# biggity.net
KiCad netlist of a schematic drawn in EAGLE
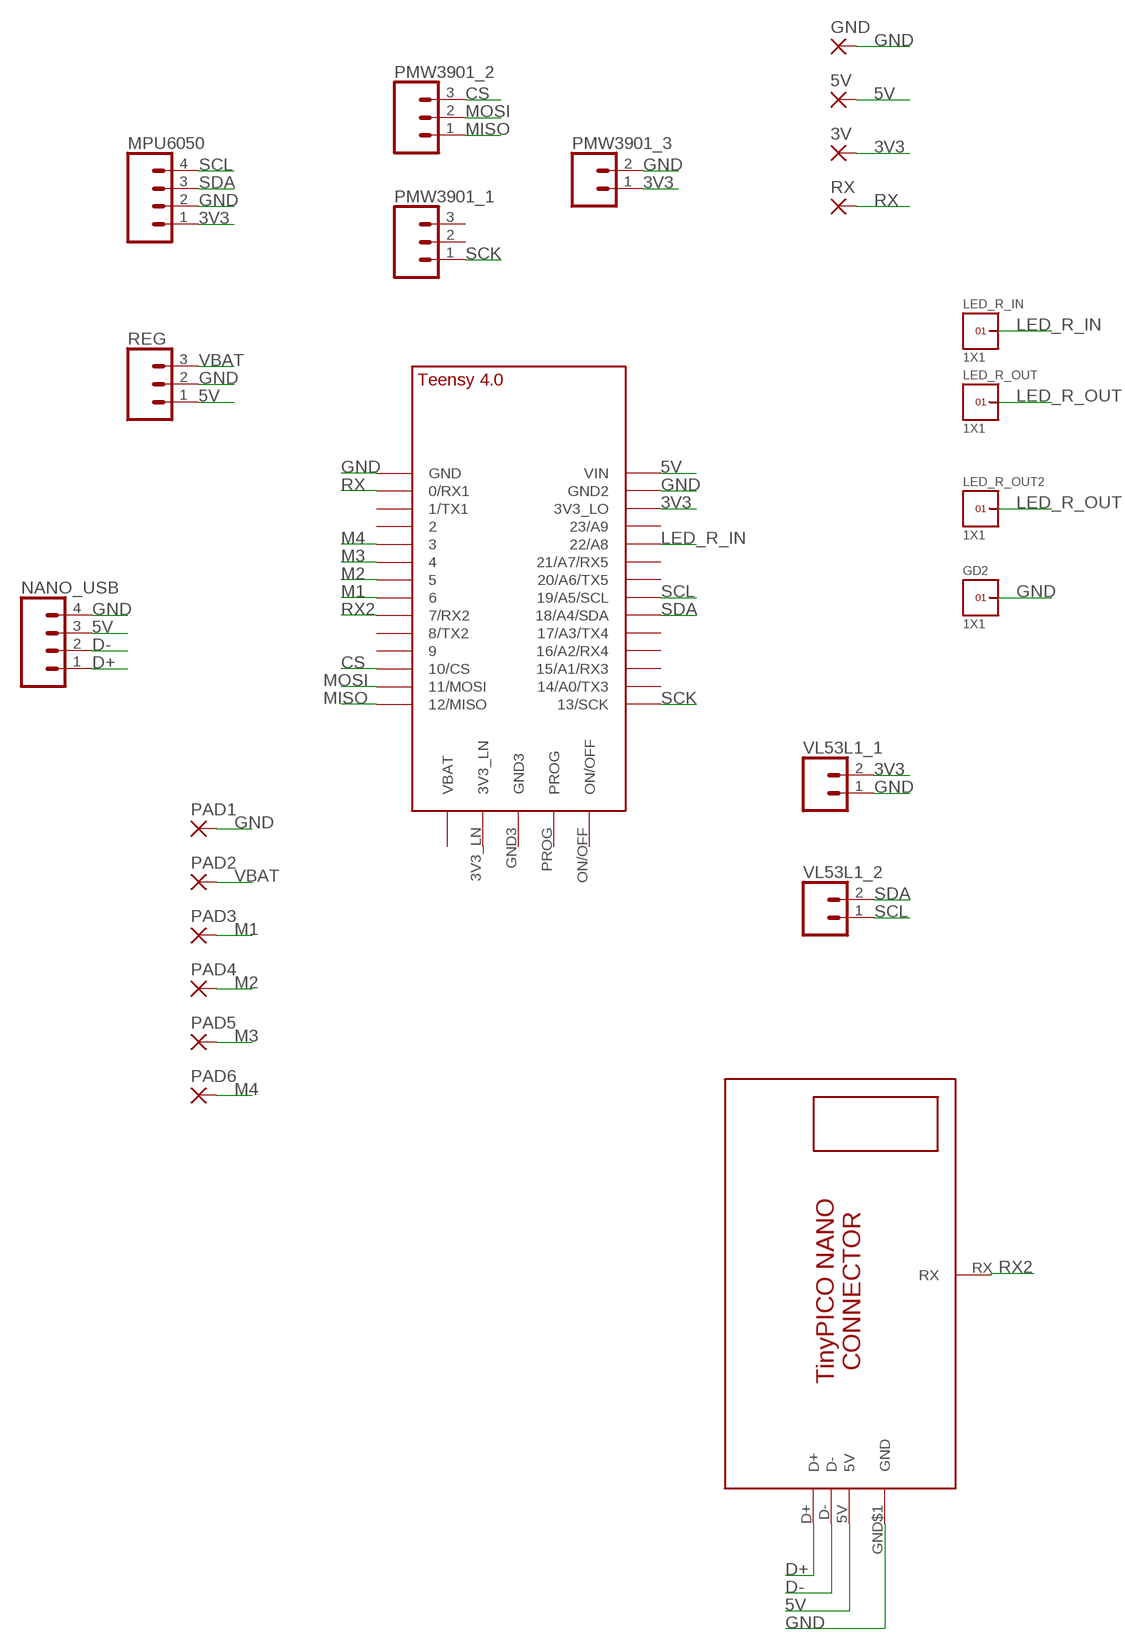
[diagram p0: schematic, sheet 1]

(export (version "E")
  (design (tool "Eeschema 10.0.6"))
  (components
    (comp (ref "3V")
      (value "SMD2")
      (footprint "eagle-import:SMD1,27-2,54")
      (libsource (lib "eagle-import") (part "SMD2"))
    )
    (comp (ref "5V")
      (value "SMD2")
      (footprint "eagle-import:SMD1,27-2,54")
      (libsource (lib "eagle-import") (part "SMD2"))
    )
    (comp (ref "GD2")
      (value "1X1")
      (footprint "eagle-import:1X1")
      (libsource (lib "eagle-import") (part "1X1"))
    )
    (comp (ref "GND")
      (value "SMD2")
      (footprint "eagle-import:SMD1,27-2,54")
      (libsource (lib "eagle-import") (part "SMD2"))
    )
    (comp (ref "LED_R_IN")
      (value "1X1")
      (footprint "eagle-import:1X1")
      (libsource (lib "eagle-import") (part "1X1"))
    )
    (comp (ref "LED_R_OUT")
      (value "1X1")
      (footprint "eagle-import:1X1")
      (libsource (lib "eagle-import") (part "1X1"))
    )
    (comp (ref "LED_R_OUT2")
      (value "1X1")
      (footprint "eagle-import:1X1")
      (libsource (lib "eagle-import") (part "1X1"))
    )
    (comp (ref "MPU6050")
      (value "CONN_041X04_NO_SILK")
      (footprint "eagle-import:1X04_NO_SILK")
      (libsource (lib "eagle-import") (part "CONN_041X04_NO_SILK"))
    )
    (comp (ref "NANO_USB")
      (value "CONN_041X04_NO_SILK")
      (footprint "eagle-import:1X04_NO_SILK")
      (libsource (lib "eagle-import") (part "CONN_041X04_NO_SILK"))
    )
    (comp (ref "PAD1")
      (value "SMD2")
      (footprint "eagle-import:SMD1,27-2,54")
      (libsource (lib "eagle-import") (part "SMD2"))
    )
    (comp (ref "PAD2")
      (value "SMD2")
      (footprint "eagle-import:SMD1,27-2,54")
      (libsource (lib "eagle-import") (part "SMD2"))
    )
    (comp (ref "PAD3")
      (value "SMD2")
      (footprint "eagle-import:SMD1,27-2,54")
      (libsource (lib "eagle-import") (part "SMD2"))
    )
    (comp (ref "PAD4")
      (value "SMD2")
      (footprint "eagle-import:SMD1,27-2,54")
      (libsource (lib "eagle-import") (part "SMD2"))
    )
    (comp (ref "PAD5")
      (value "SMD2")
      (footprint "eagle-import:SMD1,27-2,54")
      (libsource (lib "eagle-import") (part "SMD2"))
    )
    (comp (ref "PAD6")
      (value "SMD2")
      (footprint "eagle-import:SMD1,27-2,54")
      (libsource (lib "eagle-import") (part "SMD2"))
    )
    (comp (ref "PMW3901_1")
      (value "CONN_031X03_NO_SILK")
      (footprint "eagle-import:1X03_NO_SILK")
      (libsource (lib "eagle-import") (part "CONN_031X03_NO_SILK"))
    )
    (comp (ref "PMW3901_2")
      (value "CONN_031X03_NO_SILK")
      (footprint "eagle-import:1X03_NO_SILK")
      (libsource (lib "eagle-import") (part "CONN_031X03_NO_SILK"))
    )
    (comp (ref "PMW3901_3")
      (value "CONN_021X02_NO_SILK")
      (footprint "eagle-import:1X02_NO_SILK")
      (libsource (lib "eagle-import") (part "CONN_021X02_NO_SILK"))
    )
    (comp (ref "REG")
      (value "CONN_031X03_NO_SILK")
      (footprint "eagle-import:1X03_NO_SILK")
      (libsource (lib "eagle-import") (part "CONN_031X03_NO_SILK"))
    )
    (comp (ref "RX")
      (value "SMD2")
      (footprint "eagle-import:SMD1,27-2,54")
      (libsource (lib "eagle-import") (part "SMD2"))
    )
    (comp (ref "U$1")
      (value "TEENSY_4.0")
      (footprint "eagle-import:TEENSY_4.0")
      (libsource (lib "eagle-import") (part "TEENSY_4.0"))
    )
    (comp (ref "U$2")
      (value "TINYPICO-NANO-CONNECTOR")
      (footprint "eagle-import:TINYPICO-NANO-CONNECTOR")
      (libsource (lib "eagle-import") (part "TINYPICO-NANO-CONNECTOR"))
    )
    (comp (ref "VL53L1_1")
      (value "CONN_021X02_NO_SILK")
      (footprint "eagle-import:1X02_NO_SILK")
      (libsource (lib "eagle-import") (part "CONN_021X02_NO_SILK"))
    )
    (comp (ref "VL53L1_2")
      (value "CONN_021X02_NO_SILK")
      (footprint "eagle-import:1X02_NO_SILK")
      (libsource (lib "eagle-import") (part "CONN_021X02_NO_SILK"))
    )
  )
  (nets
    (net (code "1") (name "/3V3") (class "Default")
      (node (ref "3V") (pin "1") (pinfunction "P_1") (pintype "passive"))
      (node (ref "MPU6050") (pin "1") (pinfunction "1_1") (pintype "passive"))
      (node (ref "PMW3901_3") (pin "1") (pinfunction "1_1") (pintype "passive"))
      (node (ref "U$1") (pin "3V3_LO") (pinfunction "3V3_LO_3V3_LO") (pintype "bidirectional"))
      (node (ref "VL53L1_1") (pin "2") (pinfunction "2_2") (pintype "passive"))
    )
    (net (code "2") (name "/5V") (class "Default")
      (node (ref "5V") (pin "1") (pinfunction "P_1") (pintype "passive"))
      (node (ref "NANO_USB") (pin "3") (pinfunction "3_3") (pintype "passive"))
      (node (ref "REG") (pin "1") (pinfunction "1_1") (pintype "passive"))
      (node (ref "U$1") (pin "VIN") (pinfunction "VIN_VIN") (pintype "bidirectional"))
      (node (ref "U$2") (pin "5V") (pinfunction "5V_5V") (pintype "power_in"))
    )
    (net (code "3") (name "/CS") (class "Default")
      (node (ref "PMW3901_2") (pin "3") (pinfunction "3_3") (pintype "passive"))
      (node (ref "U$1") (pin "10/CS") (pinfunction "10/CS_10/CS") (pintype "bidirectional"))
    )
    (net (code "4") (name "/D+") (class "Default")
      (node (ref "NANO_USB") (pin "1") (pinfunction "1_1") (pintype "passive"))
      (node (ref "U$2") (pin "D+") (pinfunction "D+_D+") (pintype "bidirectional"))
    )
    (net (code "5") (name "/D-") (class "Default")
      (node (ref "NANO_USB") (pin "2") (pinfunction "2_2") (pintype "passive"))
      (node (ref "U$2") (pin "D-") (pinfunction "D-_D-") (pintype "bidirectional"))
    )
    (net (code "6") (name "/GND") (class "Default")
      (node (ref "GD2") (pin "1") (pinfunction "1_1") (pintype "bidirectional"))
      (node (ref "GND") (pin "1") (pinfunction "P_1") (pintype "passive"))
      (node (ref "MPU6050") (pin "2") (pinfunction "2_2") (pintype "passive"))
      (node (ref "NANO_USB") (pin "4") (pinfunction "4_4") (pintype "passive"))
      (node (ref "PAD1") (pin "1") (pinfunction "P_1") (pintype "passive"))
      (node (ref "PMW3901_3") (pin "2") (pinfunction "2_2") (pintype "passive"))
      (node (ref "REG") (pin "2") (pinfunction "2_2") (pintype "passive"))
      (node (ref "U$1") (pin "GND") (pinfunction "GND_GND") (pintype "bidirectional"))
      (node (ref "U$1") (pin "GND2") (pinfunction "GND2_GND2") (pintype "bidirectional"))
      (node (ref "U$2") (pin "GND$1") (pinfunction "GND_GND$1") (pintype "power_in"))
      (node (ref "VL53L1_1") (pin "1") (pinfunction "1_1") (pintype "passive"))
    )
    (net (code "7") (name "/LED_R_IN") (class "Default")
      (node (ref "LED_R_IN") (pin "1") (pinfunction "1_1") (pintype "bidirectional"))
      (node (ref "U$1") (pin "22/A8") (pinfunction "22/A8_22/A8") (pintype "bidirectional"))
    )
    (net (code "8") (name "/LED_R_OUT") (class "Default")
      (node (ref "LED_R_OUT") (pin "1") (pinfunction "1_1") (pintype "bidirectional"))
      (node (ref "LED_R_OUT2") (pin "1") (pinfunction "1_1") (pintype "bidirectional"))
    )
    (net (code "9") (name "/M1") (class "Default")
      (node (ref "PAD3") (pin "1") (pinfunction "P_1") (pintype "passive"))
      (node (ref "U$1") (pin "6") (pinfunction "6_6") (pintype "bidirectional"))
    )
    (net (code "10") (name "/M2") (class "Default")
      (node (ref "PAD4") (pin "1") (pinfunction "P_1") (pintype "passive"))
      (node (ref "U$1") (pin "5") (pinfunction "5_5") (pintype "bidirectional"))
    )
    (net (code "11") (name "/M3") (class "Default")
      (node (ref "PAD5") (pin "1") (pinfunction "P_1") (pintype "passive"))
      (node (ref "U$1") (pin "4/CANRX") (pinfunction "4_4/CANRX") (pintype "bidirectional"))
    )
    (net (code "12") (name "/M4") (class "Default")
      (node (ref "PAD6") (pin "1") (pinfunction "P_1") (pintype "passive"))
      (node (ref "U$1") (pin "3/CANTX") (pinfunction "3_3/CANTX") (pintype "bidirectional"))
    )
    (net (code "13") (name "/MISO") (class "Default")
      (node (ref "PMW3901_2") (pin "1") (pinfunction "1_1") (pintype "passive"))
      (node (ref "U$1") (pin "12/MISO") (pinfunction "12/MISO_12/MISO") (pintype "bidirectional"))
    )
    (net (code "14") (name "/MOSI") (class "Default")
      (node (ref "PMW3901_2") (pin "2") (pinfunction "2_2") (pintype "passive"))
      (node (ref "U$1") (pin "11/MOSI") (pinfunction "11/MOSI_11/MOSI") (pintype "bidirectional"))
    )
    (net (code "15") (name "/RX") (class "Default")
      (node (ref "RX") (pin "1") (pinfunction "P_1") (pintype "passive"))
      (node (ref "U$1") (pin "0/RX") (pinfunction "0/RX1_0/RX") (pintype "bidirectional"))
    )
    (net (code "16") (name "/RX2") (class "Default")
      (node (ref "U$1") (pin "7") (pinfunction "7/RX2_7") (pintype "bidirectional"))
      (node (ref "U$2") (pin "RX") (pinfunction "RX_RX") (pintype "bidirectional"))
    )
    (net (code "17") (name "/SCK") (class "Default")
      (node (ref "PMW3901_1") (pin "1") (pinfunction "1_1") (pintype "passive"))
      (node (ref "U$1") (pin "13/SCK") (pinfunction "13/SCK_13/SCK") (pintype "bidirectional"))
    )
    (net (code "18") (name "/SCL") (class "Default")
      (node (ref "MPU6050") (pin "4") (pinfunction "4_4") (pintype "passive"))
      (node (ref "U$1") (pin "19/A5/SCL") (pinfunction "19/A5/SCL_19/A5/SCL") (pintype "bidirectional"))
      (node (ref "VL53L1_2") (pin "1") (pinfunction "1_1") (pintype "passive"))
    )
    (net (code "19") (name "/SDA") (class "Default")
      (node (ref "MPU6050") (pin "3") (pinfunction "3_3") (pintype "passive"))
      (node (ref "U$1") (pin "18/A4/SDA") (pinfunction "18/A4/SDA_18/A4/SDA") (pintype "bidirectional"))
      (node (ref "VL53L1_2") (pin "2") (pinfunction "2_2") (pintype "passive"))
    )
    (net (code "20") (name "/VBAT") (class "Default")
      (node (ref "PAD2") (pin "1") (pinfunction "P_1") (pintype "passive"))
      (node (ref "REG") (pin "3") (pinfunction "3_3") (pintype "passive"))
    )
    (net (code "21") (name "unconnected-(PMW3901_1-Pad2)") (class "Default")
      (node (ref "PMW3901_1") (pin "2") (pinfunction "2_2") (pintype "passive"))
    )
    (net (code "22") (name "unconnected-(PMW3901_1-Pad3)") (class "Default")
      (node (ref "PMW3901_1") (pin "3") (pinfunction "3_3") (pintype "passive"))
    )
    (net (code "23") (name "unconnected-(U$1-1{slash}TX1-Pad1{slash}TX)") (class "Default")
      (node (ref "U$1") (pin "1/TX") (pinfunction "1/TX1_1/TX") (pintype "bidirectional"))
    )
    (net (code "24") (name "unconnected-(U$1-8{slash}TX2-Pad8)") (class "Default")
      (node (ref "U$1") (pin "8") (pinfunction "8/TX2_8") (pintype "bidirectional"))
    )
    (net (code "25") (name "unconnected-(U$1-9-Pad9{slash}CS)") (class "Default")
      (node (ref "U$1") (pin "9/CS") (pinfunction "9_9/CS") (pintype "bidirectional"))
    )
    (net (code "26") (name "unconnected-(U$1-14{slash}A0{slash}TX3-Pad14{slash}A0)") (class "Default")
      (node (ref "U$1") (pin "14/A0") (pinfunction "14/A0/TX3_14/A0") (pintype "bidirectional"))
    )
    (net (code "27") (name "unconnected-(U$1-15{slash}A1{slash}RX3-Pad15{slash}A1)") (class "Default")
      (node (ref "U$1") (pin "15/A1") (pinfunction "15/A1/RX3_15/A1") (pintype "bidirectional"))
    )
    (net (code "28") (name "unconnected-(U$1-16{slash}A2{slash}RX4-Pad16{slash}A2)") (class "Default")
      (node (ref "U$1") (pin "16/A2") (pinfunction "16/A2/RX4_16/A2") (pintype "bidirectional"))
    )
    (net (code "29") (name "unconnected-(U$1-17{slash}A3{slash}TX4-Pad17{slash}A3)") (class "Default")
      (node (ref "U$1") (pin "17/A3") (pinfunction "17/A3/TX4_17/A3") (pintype "bidirectional"))
    )
    (net (code "30") (name "unconnected-(U$1-20{slash}A6{slash}TX5-Pad20{slash}A6)") (class "Default")
      (node (ref "U$1") (pin "20/A6") (pinfunction "20/A6/TX5_20/A6") (pintype "bidirectional"))
    )
    (net (code "31") (name "unconnected-(U$1-21{slash}A7{slash}RX5-Pad21{slash}A7)") (class "Default")
      (node (ref "U$1") (pin "21/A7") (pinfunction "21/A7/RX5_21/A7") (pintype "bidirectional"))
    )
    (net (code "32") (name "unconnected-(U$1-Pad2)") (class "Default")
      (node (ref "U$1") (pin "2") (pinfunction "2_2") (pintype "bidirectional"))
    )
    (net (code "33") (name "unconnected-(U$1-Pad3V3_LN)") (class "Default")
      (node (ref "U$1") (pin "3V3_LN") (pinfunction "3V3_LN_3V3_LN") (pintype "bidirectional"))
    )
    (net (code "34") (name "unconnected-(U$1-Pad23{slash}A9)") (class "Default")
      (node (ref "U$1") (pin "23/A9") (pinfunction "23/A9_23/A9") (pintype "bidirectional"))
    )
    (net (code "35") (name "unconnected-(U$1-PadGND3)") (class "Default")
      (node (ref "U$1") (pin "GND3") (pinfunction "GND3_GND3") (pintype "bidirectional"))
    )
    (net (code "36") (name "unconnected-(U$1-PadON{slash}OFF)") (class "Default")
      (node (ref "U$1") (pin "ON/OFF") (pinfunction "ON/OFF_ON/OFF") (pintype "bidirectional"))
    )
    (net (code "37") (name "unconnected-(U$1-PadPROG)") (class "Default")
      (node (ref "U$1") (pin "PROG") (pinfunction "PROG_PROG") (pintype "bidirectional"))
    )
    (net (code "38") (name "unconnected-(U$1-VBAT-PadVBAT\\)") (class "Default")
      (node (ref "U$1") (pin "VBAT\\") (pinfunction "VBAT_VBAT\\") (pintype "bidirectional"))
    )
  )
)
